# Power_Supply.net
KiCad netlist of a schematic drawn in Altium Designer
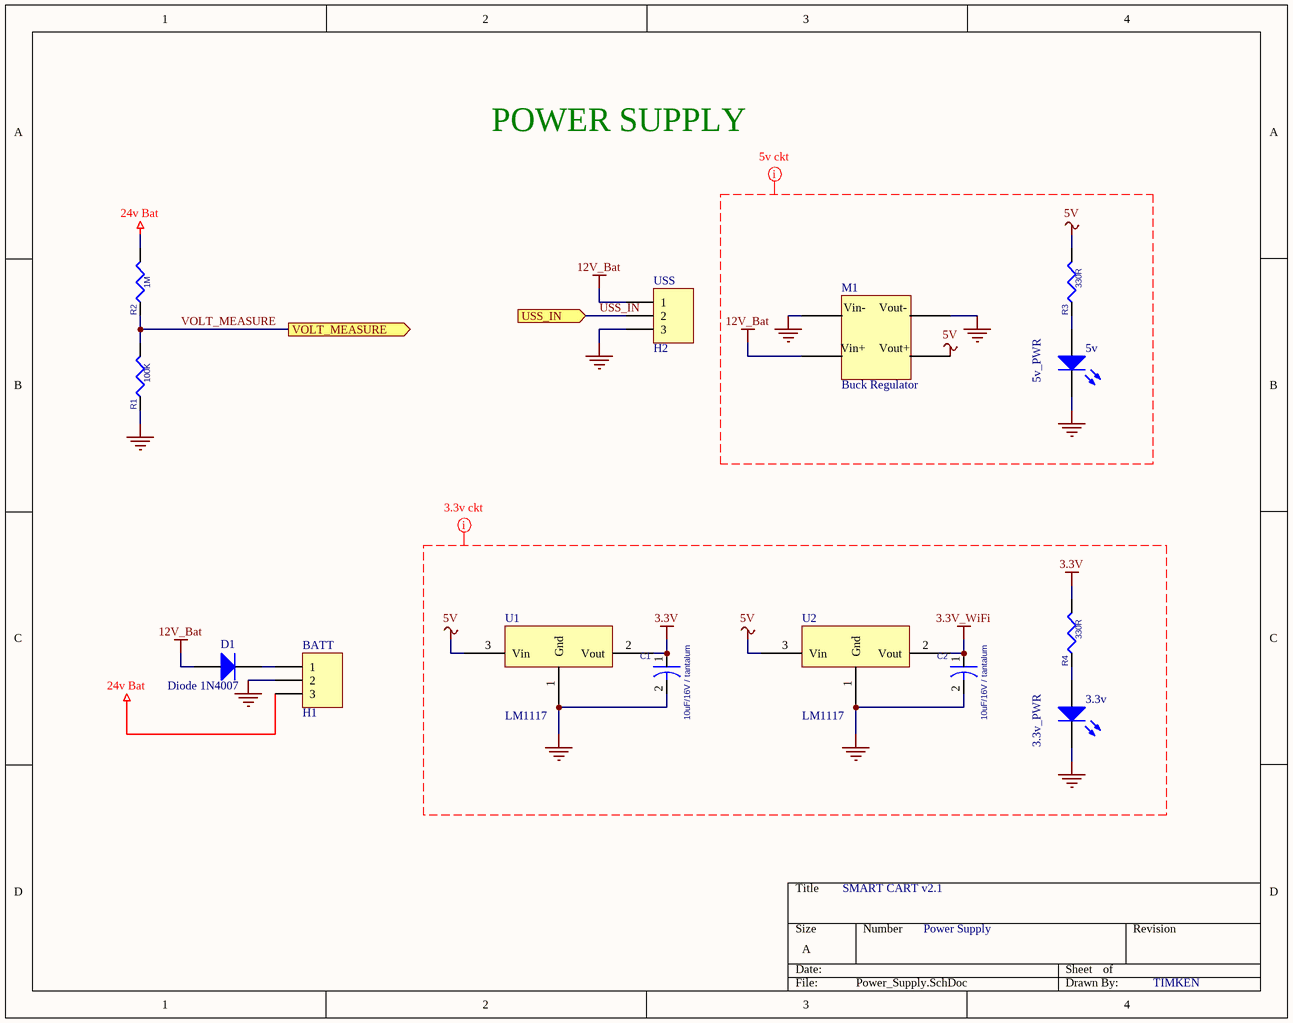
[diagram p0: Power_Supply.SchDoc]

(export (version "E")
  (design (tool "Eeschema 10.0.6"))
  (components
    (comp (ref "3.3v")
      (value "3.3v_PWR")
      (footprint "LED_SMD")
      (description "Typical INFRARED GaAs LED_throughole")
      (fields (field (name "PUBLISHER") "Altium Limited"))
      (libsource (lib "combined_cart_schematic_lib") (part "LED_SMD"))
    )
    (comp (ref "5v")
      (value "5v_PWR")
      (footprint "LED_SMD")
      (description "Typical INFRARED GaAs LED_throughole")
      (fields (field (name "PUBLISHER") "Altium Limited"))
      (libsource (lib "combined_cart_schematic_lib") (part "LED_SMD"))
    )
    (comp (ref "BATT")
      (value "H1")
      (footprint "BATTERY_3PIN")
      (description "Header, 3-Pin")
      (libsource (lib "combined_cart_schematic_lib") (part "BATTERY_3PIN"))
    )
    (comp (ref "C1")
      (value "10uF/16V / tantalum")
      (footprint "CAP_TANTALUM")
      (libsource (lib "combined_cart_schematic_lib") (part "C_0"))
    )
    (comp (ref "C2")
      (value "10uF/16V / tantalum")
      (footprint "1210")
      (libsource (lib "combined_cart_schematic_lib") (part "C_0"))
    )
    (comp (ref "D1")
      (value "Diode 1N4007")
      (footprint "D-IN4007")
      (description "1 Amp General Purpose Rectifier")
      (fields (field (name "PUBLISHER") "Altium Limited"))
      (libsource (lib "combined_cart_schematic_lib") (part "Diode 1N4007"))
    )
    (comp (ref "M1")
      (value "Buck Regulator")
      (footprint "BUCKREGULATOR")
      (description "buck regulator\\")
      (fields (field (name "PUBLISHER") "Altium Limited"))
      (libsource (lib "combined_cart_schematic_lib") (part "Regulator"))
    )
    (comp (ref "R1")
      (value "100K")
      (footprint "RES_SMD")
      (libsource (lib "combined_cart_schematic_lib") (part "RESISTOR"))
    )
    (comp (ref "R2")
      (value "1M")
      (footprint "RES_SMD")
      (libsource (lib "combined_cart_schematic_lib") (part "RESISTOR"))
    )
    (comp (ref "R3")
      (value "330R")
      (footprint "RES_SMD")
      (libsource (lib "combined_cart_schematic_lib") (part "RESISTOR"))
    )
    (comp (ref "R4")
      (value "330R")
      (footprint "RES_SMD")
      (libsource (lib "combined_cart_schematic_lib") (part "RESISTOR"))
    )
    (comp (ref "U1")
      (value "LM1117")
      (footprint "LM1117")
      (libsource (lib "combined_cart_schematic_lib") (part "LM1117"))
    )
    (comp (ref "U2")
      (value "LM1117")
      (footprint "LM1117")
      (libsource (lib "combined_cart_schematic_lib") (part "LM1117"))
    )
    (comp (ref "USS")
      (value "H2")
      (footprint "1x3_single - duplicate")
      (description "Header, 3-Pin")
      (fields (field (name "PUBLISHER") "Altium Limited"))
      (libsource (lib "combined_cart_schematic_lib") (part "Header 3"))
    )
  )
  (nets
    (net (code "1") (name "/USS_IN") (class "Default")
      (node (ref "USS") (pin "2") (pinfunction "2_2") (pintype "passive"))
    )
    (net (code "2") (name "/VOLT_MEASURE") (class "Default")
      (node (ref "R1") (pin "2") (pinfunction "2_2") (pintype "passive"))
      (node (ref "R2") (pin "1") (pinfunction "1_1") (pintype "passive"))
    )
    (net (code "3") (name "3.3V") (class "Default")
      (node (ref "C1") (pin "1") (pinfunction "1_1") (pintype "passive"))
      (node (ref "R4") (pin "2") (pinfunction "2_2") (pintype "passive"))
      (node (ref "U1") (pin "2") (pinfunction "Vout_2") (pintype "passive"))
    )
    (net (code "4") (name "3.3V_WiFi") (class "Default")
      (node (ref "C2") (pin "1") (pinfunction "1_1") (pintype "passive"))
      (node (ref "U2") (pin "2") (pinfunction "Vout_2") (pintype "passive"))
    )
    (net (code "5") (name "5V") (class "Default")
      (node (ref "M1") (pin "Vout+") (pinfunction "3_Vout+") (pintype "passive"))
      (node (ref "R3") (pin "2") (pinfunction "2_2") (pintype "passive"))
      (node (ref "U1") (pin "3") (pinfunction "Vin_3") (pintype "passive"))
      (node (ref "U2") (pin "3") (pinfunction "Vin_3") (pintype "passive"))
    )
    (net (code "6") (name "12V_Bat") (class "Default")
      (node (ref "D1") (pin "1") (pinfunction "A_1") (pintype "passive"))
      (node (ref "M1") (pin "Vin+") (pinfunction "2_Vin+") (pintype "passive"))
      (node (ref "USS") (pin "1") (pinfunction "1_1") (pintype "passive"))
    )
    (net (code "7") (name "24v Bat") (class "Default")
      (node (ref "BATT") (pin "3") (pinfunction "3_3") (pintype "passive"))
      (node (ref "R2") (pin "2") (pinfunction "2_2") (pintype "passive"))
    )
    (net (code "8") (name "GND_POWER") (class "Default")
      (node (ref "3.3v") (pin "2") (pinfunction "K_2") (pintype "passive"))
      (node (ref "5v") (pin "2") (pinfunction "K_2") (pintype "passive"))
      (node (ref "BATT") (pin "2") (pinfunction "2_2") (pintype "passive"))
      (node (ref "C1") (pin "2") (pinfunction "2_2") (pintype "passive"))
      (node (ref "C2") (pin "2") (pinfunction "2_2") (pintype "passive"))
      (node (ref "M1") (pin "Vin-") (pinfunction "0_Vin-") (pintype "passive"))
      (node (ref "M1") (pin "Vout-") (pinfunction "1_Vout-") (pintype "passive"))
      (node (ref "R1") (pin "1") (pinfunction "1_1") (pintype "passive"))
      (node (ref "U1") (pin "1") (pinfunction "Gnd_1") (pintype "power_in"))
      (node (ref "U2") (pin "1") (pinfunction "Gnd_1") (pintype "power_in"))
      (node (ref "USS") (pin "3") (pinfunction "3_3") (pintype "passive"))
    )
    (net (code "9") (name "Net-(3.3v-A)") (class "Default")
      (node (ref "3.3v") (pin "1") (pinfunction "A_1") (pintype "passive"))
      (node (ref "R4") (pin "1") (pinfunction "1_1") (pintype "passive"))
    )
    (net (code "10") (name "Net-(5v-A)") (class "Default")
      (node (ref "5v") (pin "1") (pinfunction "A_1") (pintype "passive"))
      (node (ref "R3") (pin "1") (pinfunction "1_1") (pintype "passive"))
    )
    (net (code "11") (name "Net-(D1-K)") (class "Default")
      (node (ref "BATT") (pin "1") (pinfunction "1_1") (pintype "passive"))
      (node (ref "D1") (pin "2") (pinfunction "K_2") (pintype "passive"))
    )
  )
)
